# MyFirstDesign-LDO-Schematic.net
KiCad netlist of a schematic drawn in Altium Designer
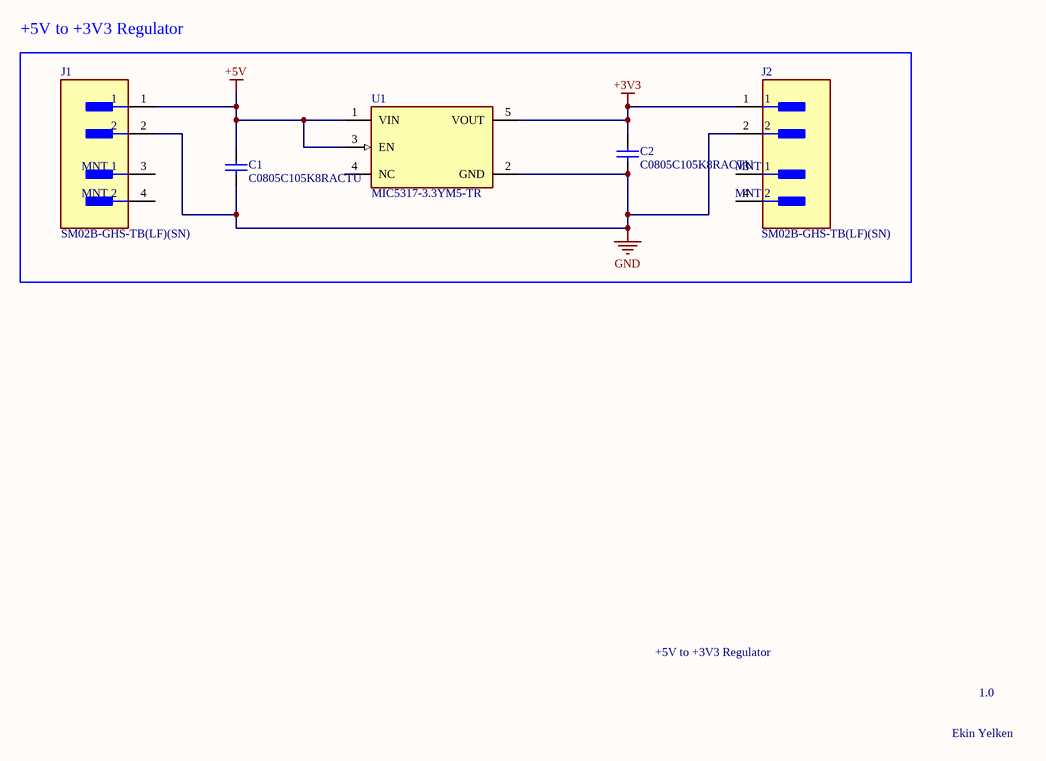
[diagram p0: MyFirstDesign-LDO-Schematic.SchDoc]

(export (version "E")
  (design (tool "Eeschema 10.0.6"))
  (components
    (comp (ref "C1")
      (value "C0805C105K8RACTU")
      (footprint "CAPC2013X100X50ML20T25")
      (fields (field (name "MANUFACTURER") "Kemet"))
      (libsource (lib "Altium Content Vault") (part "CAP"))
    )
    (comp (ref "C2")
      (value "C0805C105K8RACTU")
      (footprint "CAPC2013X100X50ML20T25")
      (fields (field (name "MANUFACTURER") "Kemet"))
      (libsource (lib "Altium Content Vault") (part "CAP"))
    )
    (comp (ref "J1")
      (value "SM02B-GHS-TB(LF)(SN)")
      (footprint "FP-SM02B-GHS-TB_LF_SN-MFG")
      (description "CONN HEADER SMD R/A 2POS 1.25MM")
      (libsource (lib "Altium Content Vault") (part "56ec3178a87b3978bdc1b3682cd516a"))
    )
    (comp (ref "J2")
      (value "SM02B-GHS-TB(LF)(SN)")
      (footprint "FP-SM02B-GHS-TB_LF_SN-MFG")
      (description "CONN HEADER SMD R/A 2POS 1.25MM")
      (libsource (lib "") (part "56ec3178a87b3978bdc1b3682cd516a_1"))
    )
    (comp (ref "U1")
      (value "MIC5317-3.3YM5-TR")
      (footprint "FP-SOT23-5LD-PL-1-MFG")
      (description "IC REG LINEAR 3.3V 150MA SOT23-5")
      (libsource (lib "Altium Content Vault") (part "0a093dae7315cdc977fd108dde87457"))
    )
  )
  (nets
    (net (code "1") (name "+3V3") (class "Default")
      (node (ref "C2") (pin "1") (pinfunction "1_1") (pintype "passive"))
      (node (ref "J2") (pin "1") (pinfunction "1_1") (pintype "passive"))
      (node (ref "U1") (pin "5") (pinfunction "VOUT_5") (pintype "power_in"))
    )
    (net (code "2") (name "+5V") (class "Default")
      (node (ref "C1") (pin "2") (pinfunction "2_2") (pintype "passive"))
      (node (ref "J1") (pin "1") (pinfunction "1_1") (pintype "passive"))
      (node (ref "U1") (pin "1") (pinfunction "VIN_1") (pintype "power_in"))
      (node (ref "U1") (pin "3") (pinfunction "EN_3") (pintype "input"))
    )
    (net (code "3") (name "GND") (class "Default")
      (node (ref "C1") (pin "1") (pinfunction "1_1") (pintype "passive"))
      (node (ref "C2") (pin "2") (pinfunction "2_2") (pintype "passive"))
      (node (ref "J1") (pin "2") (pinfunction "2_2") (pintype "passive"))
      (node (ref "J2") (pin "2") (pinfunction "2_2") (pintype "passive"))
      (node (ref "U1") (pin "2") (pinfunction "GND_2") (pintype "power_in"))
    )
    (net (code "4") (name "unconnected-(J1-MNT_1-Pad3)") (class "Default")
      (node (ref "J1") (pin "3") (pinfunction "MNT_1_3") (pintype "passive"))
    )
    (net (code "5") (name "unconnected-(J1-MNT_2-Pad4)") (class "Default")
      (node (ref "J1") (pin "4") (pinfunction "MNT_2_4") (pintype "passive"))
    )
    (net (code "6") (name "unconnected-(J2-MNT_1-Pad3)") (class "Default")
      (node (ref "J2") (pin "3") (pinfunction "MNT_1_3") (pintype "passive"))
    )
    (net (code "7") (name "unconnected-(J2-MNT_2-Pad4)") (class "Default")
      (node (ref "J2") (pin "4") (pinfunction "MNT_2_4") (pintype "passive"))
    )
    (net (code "8") (name "unconnected-(U1-NC-Pad4)") (class "Default")
      (node (ref "U1") (pin "4") (pinfunction "NC_4") (pintype "passive"))
    )
  )
)
